# button_brick_smd.net
KiCad netlist of a schematic drawn in EAGLE
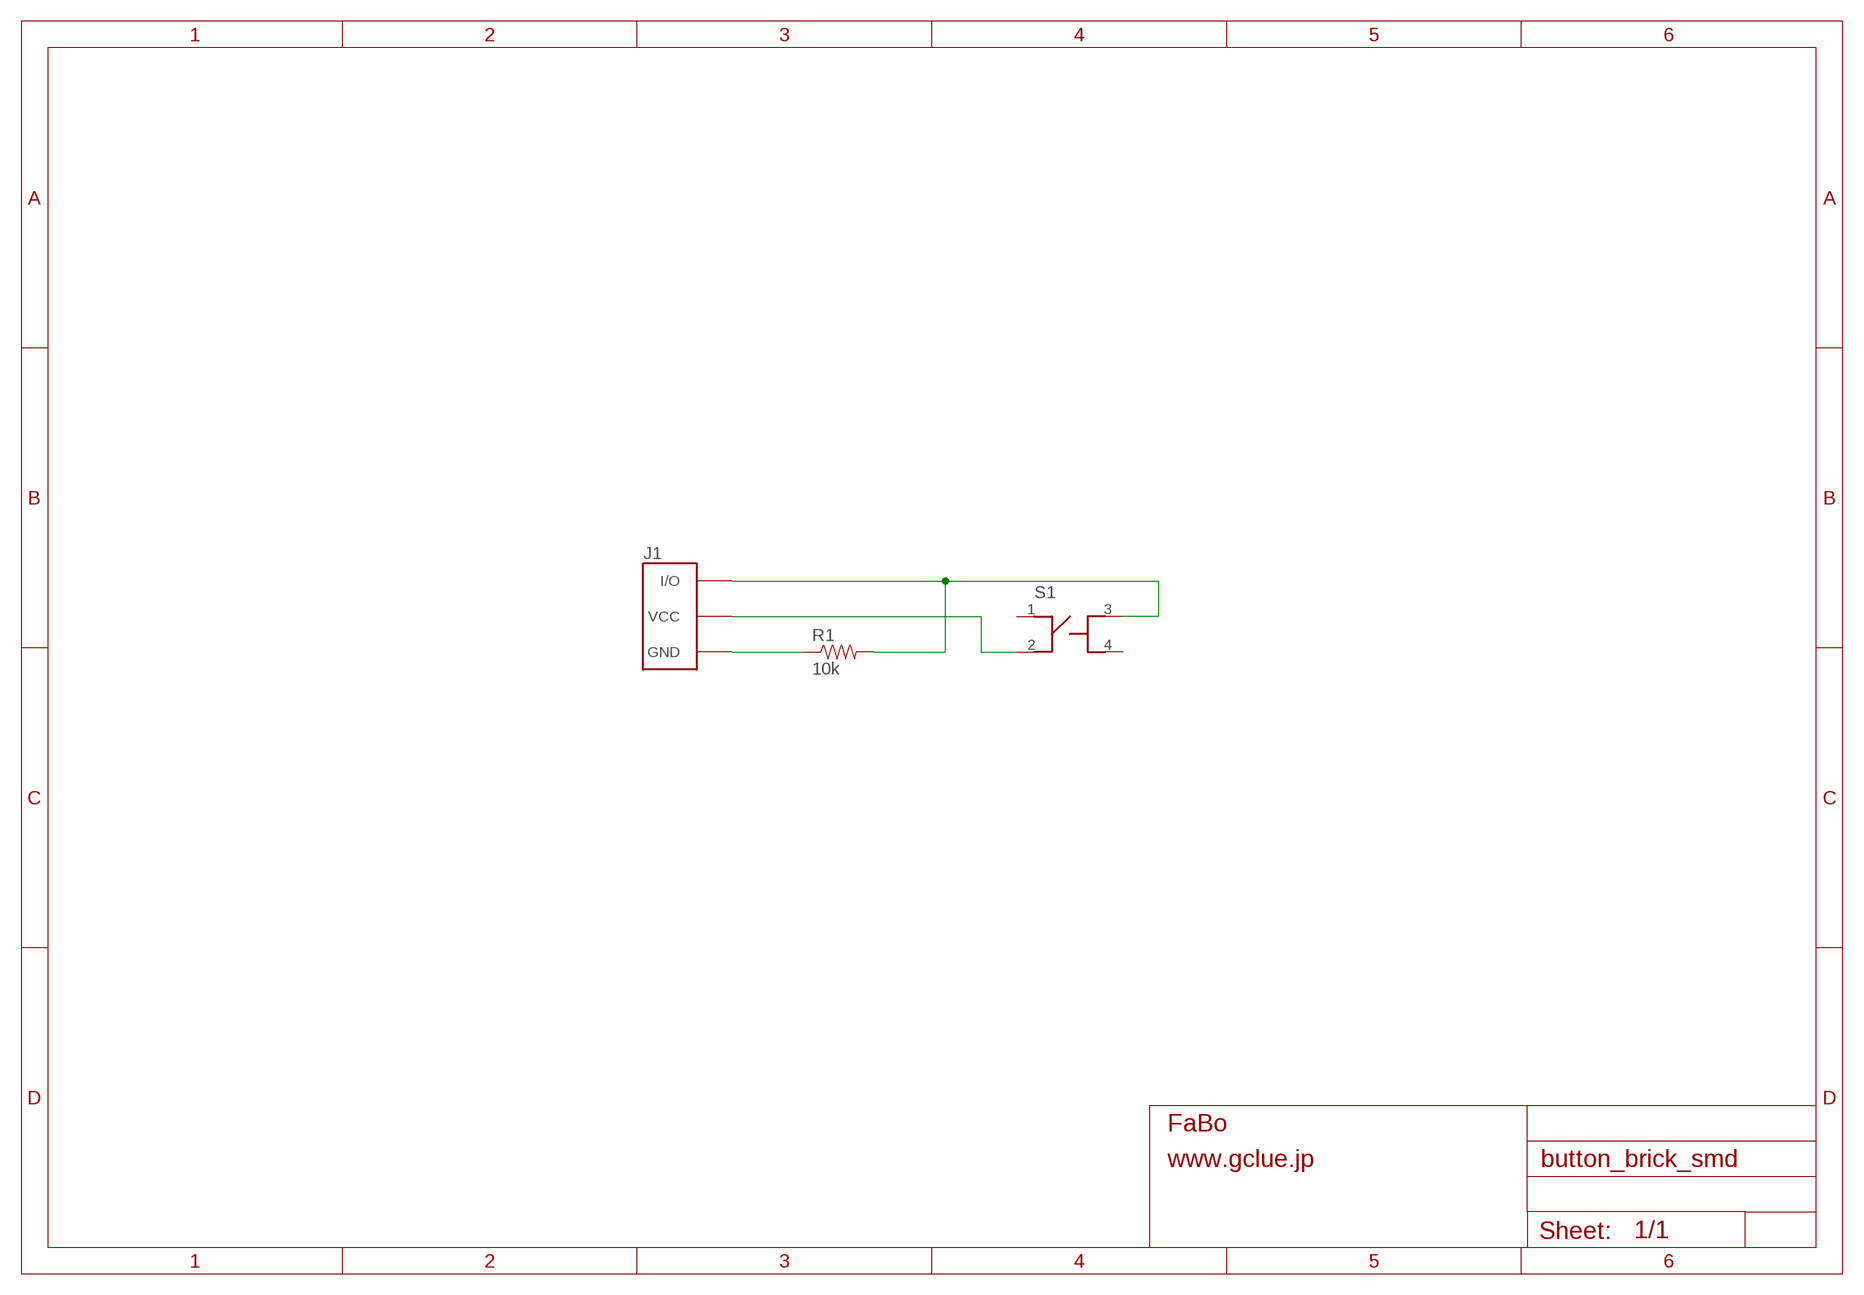
[diagram p0: schematic, sheet 1]

(export (version "E")
  (design (tool "Eeschema 10.0.6"))
  (components
    (comp (ref "J1")
      (value "BRICK_3PIN")
      (footprint "eagle-import:BRICK_3PIN")
      (libsource (lib "eagle-import") (part "BRICK_3PIN"))
    )
    (comp (ref "R1")
      (value "10k")
      (footprint "eagle-import:0603-RES")
      (libsource (lib "eagle-import") (part "RESISTOR0603"))
    )
    (comp (ref "S1")
      (value "SWITCH-LS6J2M-T")
      (footprint "eagle-import:SWITCH-LS6J2M-T")
      (libsource (lib "eagle-import") (part "SWITCH-LS6J2M-T"))
    )
  )
  (nets
    (net (code "1") (name "Net-(J1-I{slash}O)") (class "Default")
      (node (ref "J1") (pin "IN/OUT") (pinfunction "I/O_IN/OUT") (pintype "bidirectional"))
      (node (ref "R1") (pin "2") (pinfunction "2_2") (pintype "passive"))
      (node (ref "S1") (pin "3") (pinfunction "3_3") (pintype "bidirectional"))
    )
    (net (code "2") (name "Net-(J1-PadGND)") (class "Default")
      (node (ref "J1") (pin "GND") (pinfunction "GND_GND") (pintype "bidirectional"))
      (node (ref "R1") (pin "1") (pinfunction "1_1") (pintype "passive"))
    )
    (net (code "3") (name "Net-(J1-PadVCC)") (class "Default")
      (node (ref "J1") (pin "VCC") (pinfunction "VCC_VCC") (pintype "bidirectional"))
      (node (ref "S1") (pin "2") (pinfunction "2_2") (pintype "bidirectional"))
    )
    (net (code "4") (name "unconnected-(S1-Pad1)") (class "Default")
      (node (ref "S1") (pin "1") (pinfunction "1_1") (pintype "bidirectional"))
    )
    (net (code "5") (name "unconnected-(S1-Pad4)") (class "Default")
      (node (ref "S1") (pin "4") (pinfunction "4_4") (pintype "bidirectional"))
    )
  )
)
